# POW.net
KiCad netlist of a schematic drawn in Altium Designer
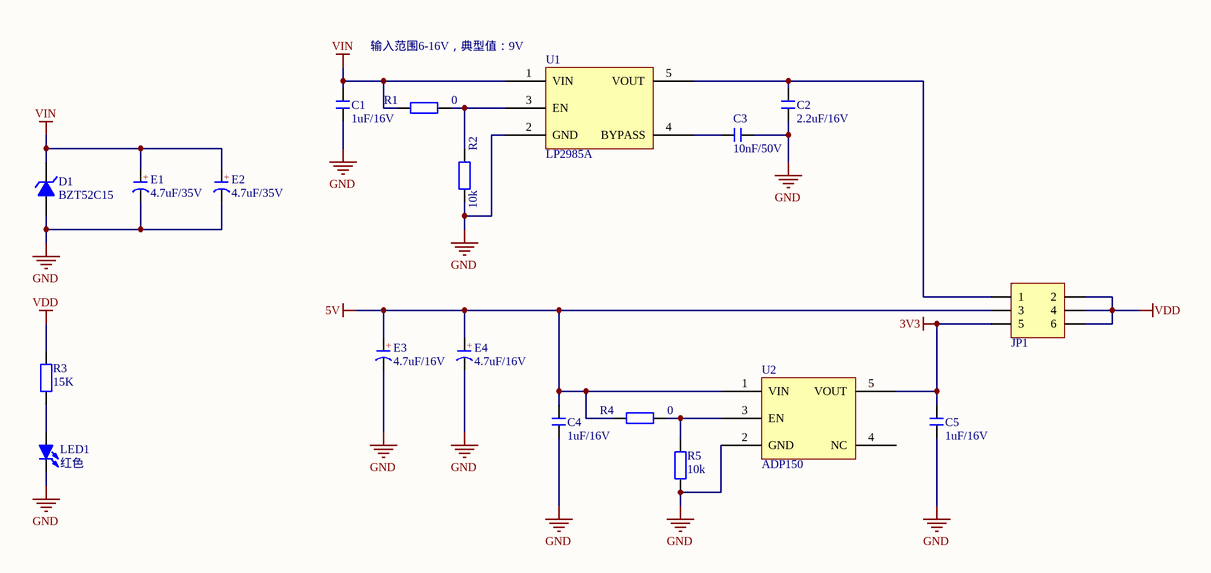
[diagram p0: POW.SchDoc]

(export (version "E")
  (design (tool "Eeschema 10.0.6"))
  (components
    (comp (ref "C1")
      (value "1uF/16V")
      (footprint "C 0402_L")
      (description "贴片电容")
      (libsource (lib "3.1   - 电阻-电容-电感") (part "C"))
    )
    (comp (ref "C2")
      (value "2.2uF/16V")
      (footprint "C 0402_L")
      (description "贴片电容")
      (libsource (lib "3.1   - 电阻-电容-电感") (part "C"))
    )
    (comp (ref "C3")
      (value "10nF/50V")
      (footprint "C 0402_L")
      (description "贴片电容 10nF/50V")
      (libsource (lib "3.1   - 电阻-电容-电感") (part "C"))
    )
    (comp (ref "C4")
      (value "1uF/16V")
      (footprint "C 0402_L")
      (description "贴片电容")
      (libsource (lib "3.1   - 电阻-电容-电感") (part "C"))
    )
    (comp (ref "C5")
      (value "1uF/16V")
      (footprint "C 0402_L")
      (description "贴片电容")
      (libsource (lib "3.1   - 电阻-电容-电感") (part "C"))
    )
    (comp (ref "D1")
      (value "BZT52C15")
      (footprint "SOD-123")
      (libsource (lib "8.1   - 二极管-整流桥") (part "IN4735A"))
    )
    (comp (ref "E1")
      (value "4.7uF/35V")
      (footprint "CD E(7343H)")
      (description "聚合物电容 4.7uF/35V")
      (libsource (lib "3.1   - 电阻-电容-电感") (part "C-CD"))
    )
    (comp (ref "E2")
      (value "4.7uF/35V")
      (footprint "CD E(7343H)")
      (description "聚合物电容 4.7uF/35V")
      (libsource (lib "3.1   - 电阻-电容-电感") (part "C-CD"))
    )
    (comp (ref "E3")
      (value "4.7uF/16V")
      (footprint "CD A(3216)")
      (description "聚合物电容 4.7uF/16V")
      (libsource (lib "3.1   - 电阻-电容-电感") (part "C-CD"))
    )
    (comp (ref "E4")
      (value "4.7uF/16V")
      (footprint "CD A(3216)")
      (description "聚合物电容 4.7uF/16V")
      (libsource (lib "3.1   - 电阻-电容-电感") (part "C-CD"))
    )
    (comp (ref "JP1")
      (value "Header3X2")
      (footprint "HDR2.54-LI-2x3P")
      (description "3*2P接插件")
      (fields (field (name "版权归属") "源创客"))
      (libsource (lib "4.5   - 接插件-脚距2.54") (part "Header 3X2"))
    )
    (comp (ref "LED1")
      (value "红色")
      (footprint "LED")
      (description "C84267")
      (libsource (lib "9.1   - LED") (part "LED-SMD"))
    )
    (comp (ref "R1")
      (value "0")
      (footprint "R 0402_L")
      (description "贴片电阻 0402 1%")
      (libsource (lib "3.1   - 电阻-电容-电感") (part "R"))
    )
    (comp (ref "R2")
      (value "10k")
      (footprint "R 0402_L")
      (description "贴片电阻")
      (libsource (lib "3.1   - 电阻-电容-电感") (part "R"))
    )
    (comp (ref "R3")
      (value "15K")
      (footprint "R 0402_L")
      (description "贴片电阻 0402 5%")
      (libsource (lib "3.1   - 电阻-电容-电感") (part "R"))
    )
    (comp (ref "R4")
      (value "0")
      (footprint "R 0402_L")
      (description "贴片电阻 0402 1%")
      (libsource (lib "3.1   - 电阻-电容-电感") (part "R"))
    )
    (comp (ref "R5")
      (value "10k")
      (footprint "R 0402_L")
      (description "贴片电阻")
      (libsource (lib "3.1   - 电阻-电容-电感") (part "R"))
    )
    (comp (ref "U1") (value "LP2985A") (footprint "SOT23-5") (libsource (lib "Schlib1") (part "LP2985A")))
    (comp (ref "U2")
      (value "ADP150")
      (footprint "SOT23-5")
      (description "ADP150AUJZ-3.3-R7")
      (libsource (lib "2021-06-09_05-08-06") (part "ADP150"))
    )
  )
  (nets
    (net (code "1") (name "3V3") (class "Default")
      (node (ref "C5") (pin "2") (pinfunction "2_2") (pintype "passive"))
      (node (ref "JP1") (pin "5") (pinfunction "5_5") (pintype "passive"))
      (node (ref "U2") (pin "5") (pinfunction "VOUT_5") (pintype "passive"))
    )
    (net (code "2") (name "5V") (class "Default")
      (node (ref "C4") (pin "2") (pinfunction "2_2") (pintype "passive"))
      (node (ref "E3") (pin "1") (pinfunction "A_1") (pintype "passive"))
      (node (ref "E4") (pin "1") (pinfunction "A_1") (pintype "passive"))
      (node (ref "JP1") (pin "3") (pinfunction "3_3") (pintype "passive"))
      (node (ref "R4") (pin "2") (pinfunction "2_2") (pintype "passive"))
      (node (ref "U2") (pin "1") (pinfunction "VIN_1") (pintype "passive"))
    )
    (net (code "3") (name "GND") (class "Default")
      (node (ref "C1") (pin "1") (pinfunction "1_1") (pintype "passive"))
      (node (ref "C2") (pin "1") (pinfunction "1_1") (pintype "passive"))
      (node (ref "C3") (pin "2") (pinfunction "2_2") (pintype "passive"))
      (node (ref "C4") (pin "1") (pinfunction "1_1") (pintype "passive"))
      (node (ref "C5") (pin "1") (pinfunction "1_1") (pintype "passive"))
      (node (ref "D1") (pin "1") (pinfunction "A_1") (pintype "passive"))
      (node (ref "E1") (pin "2") (pinfunction "K_2") (pintype "passive"))
      (node (ref "E2") (pin "2") (pinfunction "K_2") (pintype "passive"))
      (node (ref "E3") (pin "2") (pinfunction "K_2") (pintype "passive"))
      (node (ref "E4") (pin "2") (pinfunction "K_2") (pintype "passive"))
      (node (ref "LED1") (pin "2") (pinfunction "K_2") (pintype "passive"))
      (node (ref "R2") (pin "2") (pinfunction "2_2") (pintype "passive"))
      (node (ref "R5") (pin "2") (pinfunction "2_2") (pintype "passive"))
      (node (ref "U1") (pin "2") (pinfunction "GND_2") (pintype "passive"))
      (node (ref "U2") (pin "2") (pinfunction "GND_2") (pintype "passive"))
    )
    (net (code "4") (name "Net-(LED1-A)") (class "Default")
      (node (ref "LED1") (pin "1") (pinfunction "A_1") (pintype "passive"))
      (node (ref "R3") (pin "2") (pinfunction "2_2") (pintype "passive"))
    )
    (net (code "5") (name "Net-(U1-BYPASS)") (class "Default")
      (node (ref "C3") (pin "1") (pinfunction "1_1") (pintype "passive"))
      (node (ref "U1") (pin "4") (pinfunction "BYPASS_4") (pintype "passive"))
    )
    (net (code "6") (name "Net-(U1-EN)") (class "Default")
      (node (ref "R1") (pin "1") (pinfunction "1_1") (pintype "passive"))
      (node (ref "R2") (pin "1") (pinfunction "1_1") (pintype "passive"))
      (node (ref "U1") (pin "3") (pinfunction "EN_3") (pintype "passive"))
    )
    (net (code "7") (name "Net-(U1-VOUT)") (class "Default")
      (node (ref "C2") (pin "2") (pinfunction "2_2") (pintype "passive"))
      (node (ref "JP1") (pin "1") (pinfunction "1_1") (pintype "passive"))
      (node (ref "U1") (pin "5") (pinfunction "VOUT_5") (pintype "passive"))
    )
    (net (code "8") (name "Net-(U2-EN)") (class "Default")
      (node (ref "R4") (pin "1") (pinfunction "1_1") (pintype "passive"))
      (node (ref "R5") (pin "1") (pinfunction "1_1") (pintype "passive"))
      (node (ref "U2") (pin "3") (pinfunction "EN_3") (pintype "passive"))
    )
    (net (code "9") (name "VDD") (class "Default")
      (node (ref "JP1") (pin "2") (pinfunction "2_2") (pintype "passive"))
      (node (ref "JP1") (pin "4") (pinfunction "4_4") (pintype "passive"))
      (node (ref "JP1") (pin "6") (pinfunction "6_6") (pintype "passive"))
      (node (ref "R3") (pin "1") (pinfunction "1_1") (pintype "passive"))
    )
    (net (code "10") (name "VIN") (class "Default")
      (node (ref "C1") (pin "2") (pinfunction "2_2") (pintype "passive"))
      (node (ref "D1") (pin "2") (pinfunction "K_2") (pintype "passive"))
      (node (ref "E1") (pin "1") (pinfunction "A_1") (pintype "passive"))
      (node (ref "E2") (pin "1") (pinfunction "A_1") (pintype "passive"))
      (node (ref "R1") (pin "2") (pinfunction "2_2") (pintype "passive"))
      (node (ref "U1") (pin "1") (pinfunction "VIN_1") (pintype "passive"))
    )
    (net (code "11") (name "unconnected-(U2-NC-Pad4)") (class "Default")
      (node (ref "U2") (pin "4") (pinfunction "NC_4") (pintype "passive"))
    )
  )
)
